# v0_4_5.net
KiCad netlist of a schematic drawn in EAGLE
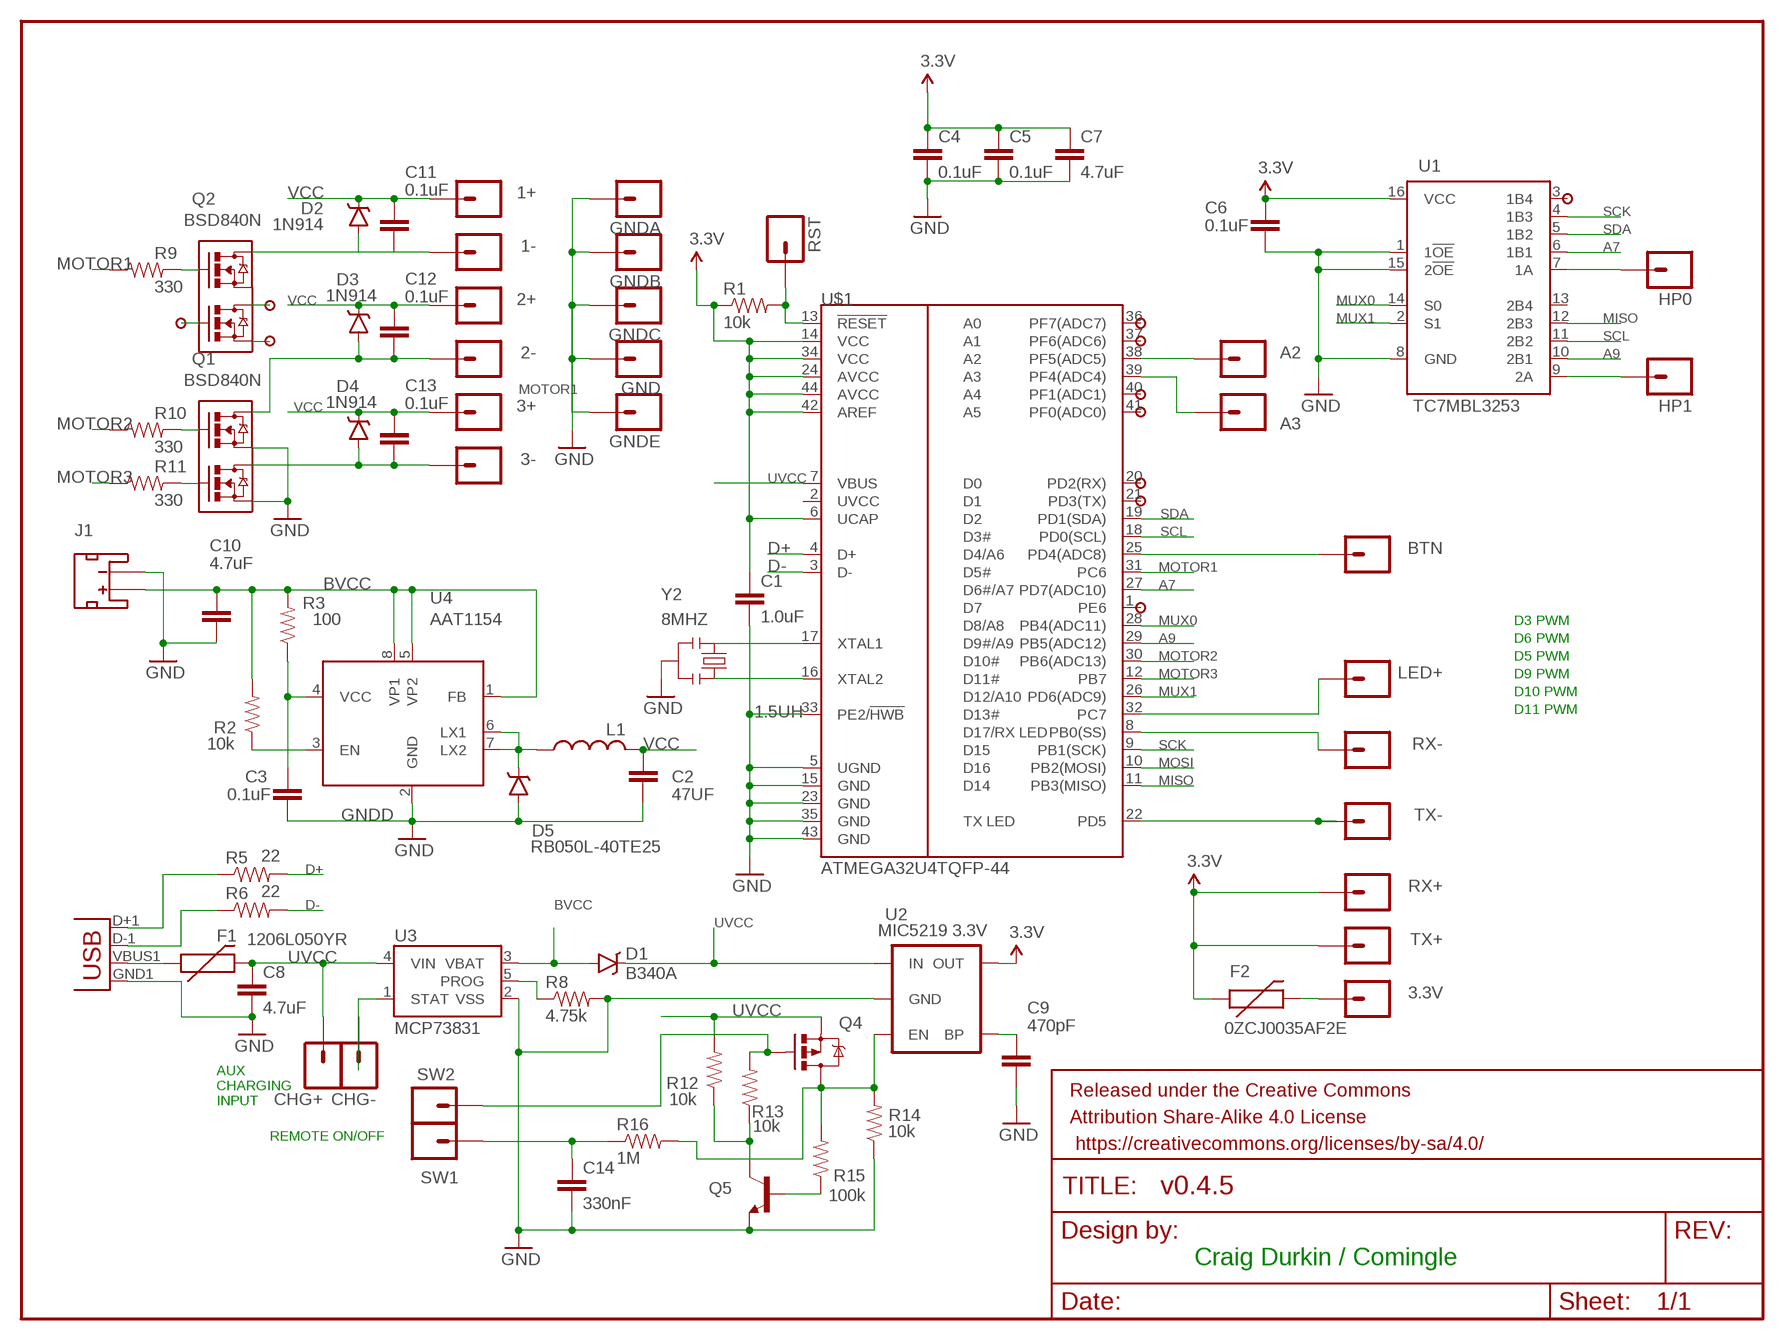
[diagram p0: schematic, sheet 1]

(export (version "E")
  (design (tool "Eeschema 10.0.6"))
  (components
    (comp (ref "1+")
      (value "M01PTH")
      (footprint "eagle-import:1X01")
      (libsource (lib "eagle-import") (part "M01PTH"))
    )
    (comp (ref "1-")
      (value "M01PTH")
      (footprint "eagle-import:1X01")
      (libsource (lib "eagle-import") (part "M01PTH"))
    )
    (comp (ref "2+")
      (value "M01PTH")
      (footprint "eagle-import:1X01")
      (libsource (lib "eagle-import") (part "M01PTH"))
    )
    (comp (ref "2-")
      (value "M01PTH")
      (footprint "eagle-import:1X01")
      (libsource (lib "eagle-import") (part "M01PTH"))
    )
    (comp (ref "3+")
      (value "M01PTH")
      (footprint "eagle-import:1X01")
      (libsource (lib "eagle-import") (part "M01PTH"))
    )
    (comp (ref "3-")
      (value "M01PTH")
      (footprint "eagle-import:1X01")
      (libsource (lib "eagle-import") (part "M01PTH"))
    )
    (comp (ref "3.3V")
      (value "M01PTH")
      (footprint "eagle-import:1X01")
      (libsource (lib "eagle-import") (part "M01PTH"))
    )
    (comp (ref "A2")
      (value "M01PTH")
      (footprint "eagle-import:1X01")
      (libsource (lib "eagle-import") (part "M01PTH"))
    )
    (comp (ref "A3")
      (value "M01PTH")
      (footprint "eagle-import:1X01")
      (libsource (lib "eagle-import") (part "M01PTH"))
    )
    (comp (ref "BTN")
      (value "M01PTH")
      (footprint "eagle-import:1X01")
      (libsource (lib "eagle-import") (part "M01PTH"))
    )
    (comp (ref "C1")
      (value "1.0uF")
      (footprint "eagle-import:0603-CAP")
      (libsource (lib "eagle-import") (part "CAP0603-CAP"))
    )
    (comp (ref "C2")
      (value "47UF")
      (footprint "eagle-import:0805")
      (libsource (lib "eagle-import") (part "v0.4.5_CAP0805"))
    )
    (comp (ref "C3")
      (value "0.1uF")
      (footprint "eagle-import:0603-CAP")
      (libsource (lib "eagle-import") (part "SparkFun-Passives_CAP0603-CAP"))
    )
    (comp (ref "C4")
      (value "0.1uF")
      (footprint "eagle-import:0603-CAP")
      (libsource (lib "eagle-import") (part "SparkFun-Passives_CAP0603-CAP"))
    )
    (comp (ref "C5")
      (value "0.1uF")
      (footprint "eagle-import:0603-CAP")
      (libsource (lib "eagle-import") (part "SparkFun-Passives_CAP0603-CAP"))
    )
    (comp (ref "C6")
      (value "0.1uF")
      (footprint "eagle-import:0603-CAP")
      (libsource (lib "eagle-import") (part "SparkFun-Passives_CAP0603-CAP"))
    )
    (comp (ref "C7")
      (value "4.7uF")
      (footprint "eagle-import:0603-CAP")
      (libsource (lib "eagle-import") (part "SparkFun-Passives_CAP0603-CAP"))
    )
    (comp (ref "C8")
      (value "4.7uF")
      (footprint "eagle-import:1206")
      (libsource (lib "eagle-import") (part "SparkFun-Passives_CAP1206"))
    )
    (comp (ref "C9")
      (value "470pF")
      (footprint "eagle-import:0603-CAP")
      (libsource (lib "eagle-import") (part "CAP0603-CAP"))
    )
    (comp (ref "C10")
      (value "4.7uF")
      (footprint "eagle-import:1206")
      (libsource (lib "eagle-import") (part "SparkFun-Passives_CAP1206"))
    )
    (comp (ref "C11")
      (value "0.1uF")
      (footprint "eagle-import:0603-CAP")
      (libsource (lib "eagle-import") (part "CAP0603-CAP"))
    )
    (comp (ref "C12")
      (value "0.1uF")
      (footprint "eagle-import:0603-CAP")
      (libsource (lib "eagle-import") (part "CAP0603-CAP"))
    )
    (comp (ref "C13")
      (value "0.1uF")
      (footprint "eagle-import:0603-CAP")
      (libsource (lib "eagle-import") (part "CAP0603-CAP"))
    )
    (comp (ref "C14")
      (value "330nF")
      (footprint "eagle-import:0603-CAP")
      (libsource (lib "eagle-import") (part "CAP0603-CAP"))
    )
    (comp (ref "CHG+")
      (value "M01PTH")
      (footprint "eagle-import:1X01")
      (libsource (lib "eagle-import") (part "M01PTH"))
    )
    (comp (ref "CHG-")
      (value "M01PTH")
      (footprint "eagle-import:1X01")
      (libsource (lib "eagle-import") (part "M01PTH"))
    )
    (comp (ref "D1")
      (value "B340A")
      (footprint "eagle-import:SMA-DIODE")
      (libsource (lib "eagle-import") (part "DIODE-SCHOTTKY-B340A"))
    )
    (comp (ref "D2")
      (value "1N914")
      (footprint "eagle-import:SOD-323")
      (libsource (lib "eagle-import") (part "BAT20JFILM"))
    )
    (comp (ref "D3")
      (value "1N914")
      (footprint "eagle-import:SOD-323")
      (libsource (lib "eagle-import") (part "BAT20JFILM"))
    )
    (comp (ref "D4")
      (value "1N914")
      (footprint "eagle-import:SOD-323")
      (libsource (lib "eagle-import") (part "BAT20JFILM"))
    )
    (comp (ref "D5")
      (value "RB050L-40TE25")
      (footprint "eagle-import:SMA-DIODE")
      (libsource (lib "eagle-import") (part "v0.4.5_DIODE-SCHOTTKY-B340A"))
    )
    (comp (ref "F1")
      (value "1206L050YR")
      (footprint "eagle-import:PTC-1206")
      (libsource (lib "eagle-import") (part "PTCSMD"))
    )
    (comp (ref "F2")
      (value "0ZCJ0035AF2E")
      (footprint "eagle-import:PTC-1206")
      (libsource (lib "eagle-import") (part "PTCSMD"))
    )
    (comp (ref "FRAME1")
      (value "FRAME-LETTER")
      (footprint "eagle-import:CREATIVE_COMMONS")
      (libsource (lib "eagle-import") (part "FRAME-LETTER"))
    )
    (comp (ref "GND")
      (value "M01PTH")
      (footprint "eagle-import:1X01")
      (libsource (lib "eagle-import") (part "M01PTH"))
    )
    (comp (ref "GNDA")
      (value "M01PTH")
      (footprint "eagle-import:1X01")
      (libsource (lib "eagle-import") (part "M01PTH"))
    )
    (comp (ref "GNDB")
      (value "M01PTH")
      (footprint "eagle-import:1X01")
      (libsource (lib "eagle-import") (part "M01PTH"))
    )
    (comp (ref "GNDC")
      (value "M01PTH")
      (footprint "eagle-import:1X01")
      (libsource (lib "eagle-import") (part "M01PTH"))
    )
    (comp (ref "GNDE")
      (value "M01PTH")
      (footprint "eagle-import:1X01")
      (libsource (lib "eagle-import") (part "M01PTH"))
    )
    (comp (ref "HP0")
      (value "M01PTH")
      (footprint "eagle-import:1X01")
      (libsource (lib "eagle-import") (part "M01PTH"))
    )
    (comp (ref "HP1")
      (value "M01PTH")
      (footprint "eagle-import:1X01")
      (libsource (lib "eagle-import") (part "M01PTH"))
    )
    (comp (ref "J1")
      (value "JST_2MM_MALE")
      (footprint "eagle-import:JST-2-SMD")
      (libsource (lib "eagle-import") (part "JST_2MM_MALE"))
    )
    (comp (ref "JP4")
      (value "USB")
      (footprint "eagle-import:USB-B-MICRO-SMD_V03")
      (libsource (lib "eagle-import") (part "USB"))
    )
    (comp (ref "L1")
      (value "1.5UH")
      (footprint "eagle-import:CHOKE_5MM")
      (libsource (lib "eagle-import") (part "LQH5BPN1R5NT0L_INDUCTOR"))
    )
    (comp (ref "LED+")
      (value "M01PTH")
      (footprint "eagle-import:1X01")
      (libsource (lib "eagle-import") (part "M01PTH"))
    )
    (comp (ref "PD2")
      (value "040_PAD_030_HOLE")
      (footprint "eagle-import:040_PAD_O30_HOLE")
      (libsource (lib "eagle-import") (part "040_PAD_030_HOLE"))
    )
    (comp (ref "PD3")
      (value "040_PAD_030_HOLE")
      (footprint "eagle-import:040_PAD_O30_HOLE")
      (libsource (lib "eagle-import") (part "040_PAD_030_HOLE"))
    )
    (comp (ref "PD4")
      (value "040_PAD_030_HOLE")
      (footprint "eagle-import:040_PAD_O30_HOLE")
      (libsource (lib "eagle-import") (part "040_PAD_030_HOLE"))
    )
    (comp (ref "PD5")
      (value "040_PAD_030_HOLE")
      (footprint "eagle-import:040_PAD_O30_HOLE")
      (libsource (lib "eagle-import") (part "040_PAD_030_HOLE"))
    )
    (comp (ref "PD6")
      (value "040_PAD_030_HOLE")
      (footprint "eagle-import:040_PAD_O30_HOLE")
      (libsource (lib "eagle-import") (part "040_PAD_030_HOLE"))
    )
    (comp (ref "PD7")
      (value "040_PAD_030_HOLE")
      (footprint "eagle-import:040_PAD_O30_HOLE")
      (libsource (lib "eagle-import") (part "040_PAD_030_HOLE"))
    )
    (comp (ref "PD8")
      (value "040_PAD_030_HOLE")
      (footprint "eagle-import:040_PAD_O30_HOLE")
      (libsource (lib "eagle-import") (part "040_PAD_030_HOLE"))
    )
    (comp (ref "PD9")
      (value "040_PAD_030_HOLE")
      (footprint "eagle-import:040_PAD_O30_HOLE")
      (libsource (lib "eagle-import") (part "040_PAD_030_HOLE"))
    )
    (comp (ref "PD10")
      (value "040_PAD_030_HOLE")
      (footprint "eagle-import:040_PAD_O30_HOLE")
      (libsource (lib "eagle-import") (part "040_PAD_030_HOLE"))
    )
    (comp (ref "PD11")
      (value "040_PAD_030_HOLE")
      (footprint "eagle-import:040_PAD_O30_HOLE")
      (libsource (lib "eagle-import") (part "040_PAD_030_HOLE"))
    )
    (comp (ref "PD12")
      (value "040_PAD_030_HOLE")
      (footprint "eagle-import:040_PAD_O30_HOLE")
      (libsource (lib "eagle-import") (part "040_PAD_030_HOLE"))
    )
    (comp (ref "Q1")
      (value "BSD840N")
      (footprint "eagle-import:PG-SOT-363")
      (libsource (lib "eagle-import") (part "BSD840N"))
    )
    (comp (ref "Q2")
      (value "BSD840N")
      (footprint "eagle-import:PG-SOT-363")
      (libsource (lib "eagle-import") (part "BSD840N"))
    )
    (comp (ref "Q4")
      (value "NTS2101PT1G")
      (footprint "eagle-import:SOT23-3")
      (libsource (lib "eagle-import") (part "MOSFET-PCHANNEL"))
    )
    (comp (ref "Q5")
      (value "MMBT2222A")
      (footprint "eagle-import:SOT23-3")
      (libsource (lib "eagle-import") (part "TRANSISTOR_NPNMMBT2222A"))
    )
    (comp (ref "R1")
      (value "10k")
      (footprint "eagle-import:0603-RES")
      (libsource (lib "eagle-import") (part "RESISTOR0603-RES"))
    )
    (comp (ref "R2")
      (value "10k")
      (footprint "eagle-import:0603-RES")
      (libsource (lib "eagle-import") (part "RESISTOR0603-RES"))
    )
    (comp (ref "R3")
      (value "100")
      (footprint "eagle-import:0603-RES")
      (libsource (lib "eagle-import") (part "RESISTOR0603-RES"))
    )
    (comp (ref "R5")
      (value "22")
      (footprint "eagle-import:0603-RES")
      (libsource (lib "eagle-import") (part "RESISTOR0603-RES"))
    )
    (comp (ref "R6")
      (value "22")
      (footprint "eagle-import:0603-RES")
      (libsource (lib "eagle-import") (part "RESISTOR0603-RES"))
    )
    (comp (ref "R8")
      (value "4.75k")
      (footprint "eagle-import:0603-RES")
      (libsource (lib "eagle-import") (part "RESISTOR0603-RES"))
    )
    (comp (ref "R9")
      (value "330")
      (footprint "eagle-import:0603-RES")
      (libsource (lib "eagle-import") (part "RESISTOR0603-RES"))
    )
    (comp (ref "R10")
      (value "330")
      (footprint "eagle-import:0603-RES")
      (libsource (lib "eagle-import") (part "RESISTOR0603-RES"))
    )
    (comp (ref "R11")
      (value "330")
      (footprint "eagle-import:0603-RES")
      (libsource (lib "eagle-import") (part "RESISTOR0603-RES"))
    )
    (comp (ref "R12")
      (value "10k")
      (footprint "eagle-import:0603-RES")
      (libsource (lib "eagle-import") (part "RESISTOR0603-RES"))
    )
    (comp (ref "R13")
      (value "10k")
      (footprint "eagle-import:0603-RES")
      (libsource (lib "eagle-import") (part "RESISTOR0603-RES"))
    )
    (comp (ref "R14")
      (value "10k")
      (footprint "eagle-import:0603-RES")
      (libsource (lib "eagle-import") (part "RESISTOR0603-RES"))
    )
    (comp (ref "R15")
      (value "100k")
      (footprint "eagle-import:0603-RES")
      (libsource (lib "eagle-import") (part "RESISTOR0603-RES"))
    )
    (comp (ref "R16")
      (value "1M")
      (footprint "eagle-import:0603-RES")
      (libsource (lib "eagle-import") (part "RESISTOR0603-RES"))
    )
    (comp (ref "RST")
      (value "M01PTH")
      (footprint "eagle-import:1X01")
      (libsource (lib "eagle-import") (part "M01PTH"))
    )
    (comp (ref "RX+")
      (value "M01PTH")
      (footprint "eagle-import:1X01")
      (libsource (lib "eagle-import") (part "M01PTH"))
    )
    (comp (ref "RX-")
      (value "M01PTH")
      (footprint "eagle-import:1X01")
      (libsource (lib "eagle-import") (part "M01PTH"))
    )
    (comp (ref "SW1")
      (value "M01PTH")
      (footprint "eagle-import:1X01")
      (libsource (lib "eagle-import") (part "M01PTH"))
    )
    (comp (ref "SW2")
      (value "M01PTH")
      (footprint "eagle-import:1X01")
      (libsource (lib "eagle-import") (part "M01PTH"))
    )
    (comp (ref "TX+")
      (value "M01PTH")
      (footprint "eagle-import:1X01")
      (libsource (lib "eagle-import") (part "M01PTH"))
    )
    (comp (ref "TX-")
      (value "M01PTH")
      (footprint "eagle-import:1X01")
      (libsource (lib "eagle-import") (part "M01PTH"))
    )
    (comp (ref "U$1")
      (value "ATMEGA32U4TQFP-44")
      (footprint "eagle-import:TQFP44")
      (libsource (lib "eagle-import") (part "ATMEGA32U4TQFP-44"))
    )
    (comp (ref "U1")
      (value "TC7MBL3253")
      (footprint "eagle-import:SSOP16-PRACTICE")
      (libsource (lib "eagle-import") (part "TC7MBL3253"))
    )
    (comp (ref "U2")
      (value "MIC5219 3.3V")
      (footprint "eagle-import:SOT23-5")
      (libsource (lib "eagle-import") (part "V_REG_MIC52193.3V"))
    )
    (comp (ref "U3")
      (value "MCP73831")
      (footprint "eagle-import:SOT23-5")
      (libsource (lib "eagle-import") (part "MCP73831"))
    )
    (comp (ref "U4")
      (value "AAT1154")
      (footprint "eagle-import:SOP-8")
      (libsource (lib "eagle-import") (part "AAT1154"))
    )
    (comp (ref "Y2")
      (value "8MHZ")
      (footprint "eagle-import:RESONATOR-SMD")
      (libsource (lib "eagle-import") (part "RESONATOR8MHZ"))
    )
  )
  (nets
    (net (code "1") (name "/A7") (class "Default")
      (node (ref "U$1") (pin "27") (pinfunction "PD7(ADC10)_27") (pintype "bidirectional"))
      (node (ref "U1") (pin "6") (pinfunction "1B1_6") (pintype "bidirectional"))
    )
    (net (code "2") (name "/A9") (class "Default")
      (node (ref "U$1") (pin "29") (pinfunction "PB5(ADC12)_29") (pintype "bidirectional"))
      (node (ref "U1") (pin "10") (pinfunction "2B1_10") (pintype "bidirectional"))
    )
    (net (code "3") (name "/BVCC") (class "Default")
      (node (ref "C10") (pin "1") (pinfunction "1_1") (pintype "passive"))
      (node (ref "D1") (pin "A") (pinfunction "A_A") (pintype "passive"))
      (node (ref "J1") (pin "2") (pinfunction "+_2") (pintype "bidirectional"))
      (node (ref "R2") (pin "2") (pinfunction "2_2") (pintype "passive"))
      (node (ref "R3") (pin "2") (pinfunction "2_2") (pintype "passive"))
      (node (ref "U3") (pin "3") (pinfunction "VBAT_3") (pintype "power_in"))
      (node (ref "U4") (pin "1") (pinfunction "FB_1") (pintype "input"))
      (node (ref "U4") (pin "5") (pinfunction "VP2_5") (pintype "power_in"))
      (node (ref "U4") (pin "8") (pinfunction "VP1_8") (pintype "power_in"))
    )
    (net (code "4") (name "/D+") (class "Default")
      (node (ref "R5") (pin "2") (pinfunction "2_2") (pintype "passive"))
      (node (ref "U$1") (pin "4") (pinfunction "D+_4") (pintype "bidirectional"))
    )
    (net (code "5") (name "/D-") (class "Default")
      (node (ref "R6") (pin "2") (pinfunction "2_2") (pintype "passive"))
      (node (ref "U$1") (pin "3") (pinfunction "D-_3") (pintype "bidirectional"))
    )
    (net (code "6") (name "/MISO") (class "Default")
      (node (ref "U$1") (pin "11") (pinfunction "PB3(MISO)_11") (pintype "bidirectional"))
      (node (ref "U1") (pin "12") (pinfunction "2B3_12") (pintype "bidirectional"))
    )
    (net (code "7") (name "/MOSI") (class "Default")
      (node (ref "U$1") (pin "10") (pinfunction "PB2(MOSI)_10") (pintype "bidirectional"))
    )
    (net (code "8") (name "/MOTOR1") (class "Default")
      (node (ref "R9") (pin "1") (pinfunction "1_1") (pintype "passive"))
      (node (ref "U$1") (pin "31") (pinfunction "PC6_31") (pintype "bidirectional"))
    )
    (net (code "9") (name "/MOTOR2") (class "Default")
      (node (ref "R10") (pin "1") (pinfunction "1_1") (pintype "passive"))
      (node (ref "U$1") (pin "30") (pinfunction "PB6(ADC13)_30") (pintype "bidirectional"))
    )
    (net (code "10") (name "/MOTOR3") (class "Default")
      (node (ref "R11") (pin "1") (pinfunction "1_1") (pintype "passive"))
      (node (ref "U$1") (pin "12") (pinfunction "PB7_12") (pintype "bidirectional"))
    )
    (net (code "11") (name "/MUX0") (class "Default")
      (node (ref "U$1") (pin "28") (pinfunction "PB4(ADC11)_28") (pintype "bidirectional"))
      (node (ref "U1") (pin "14") (pinfunction "S0_14") (pintype "bidirectional"))
    )
    (net (code "12") (name "/MUX1") (class "Default")
      (node (ref "U$1") (pin "26") (pinfunction "PD6(ADC9)_26") (pintype "bidirectional"))
      (node (ref "U1") (pin "2") (pinfunction "S1_2") (pintype "bidirectional"))
    )
    (net (code "13") (name "/SCK") (class "Default")
      (node (ref "U$1") (pin "9") (pinfunction "PB1(SCK)_9") (pintype "bidirectional"))
      (node (ref "U1") (pin "4") (pinfunction "1B3_4") (pintype "bidirectional"))
    )
    (net (code "14") (name "/SCL") (class "Default")
      (node (ref "U$1") (pin "18") (pinfunction "PD0(SCL)_18") (pintype "bidirectional"))
      (node (ref "U1") (pin "11") (pinfunction "2B2_11") (pintype "bidirectional"))
    )
    (net (code "15") (name "/SDA") (class "Default")
      (node (ref "U$1") (pin "19") (pinfunction "PD1(SDA)_19") (pintype "bidirectional"))
      (node (ref "U1") (pin "5") (pinfunction "1B2_5") (pintype "bidirectional"))
    )
    (net (code "16") (name "/UVCC") (class "Default")
      (node (ref "C8") (pin "1") (pinfunction "1_1") (pintype "passive"))
      (node (ref "CHG+") (pin "1") (pinfunction "1_1") (pintype "passive"))
      (node (ref "D1") (pin "C") (pinfunction "C_C") (pintype "passive"))
      (node (ref "F1") (pin "2") (pinfunction "2_2") (pintype "bidirectional"))
      (node (ref "Q4") (pin "2") (pinfunction "S_2") (pintype "passive"))
      (node (ref "R12") (pin "2") (pinfunction "2_2") (pintype "passive"))
      (node (ref "U$1") (pin "7") (pinfunction "VBUS_7") (pintype "bidirectional"))
      (node (ref "U2") (pin "1") (pinfunction "IN_1") (pintype "input"))
      (node (ref "U3") (pin "4") (pinfunction "VIN_4") (pintype "power_in"))
    )
    (net (code "17") (name "3.3V") (class "Default")
      (node (ref "1+") (pin "1") (pinfunction "1_1") (pintype "passive"))
      (node (ref "2+") (pin "1") (pinfunction "1_1") (pintype "passive"))
      (node (ref "3+") (pin "1") (pinfunction "1_1") (pintype "passive"))
      (node (ref "C1") (pin "1") (pinfunction "1_1") (pintype "passive"))
      (node (ref "C11") (pin "1") (pinfunction "1_1") (pintype "passive"))
      (node (ref "C12") (pin "1") (pinfunction "1_1") (pintype "passive"))
      (node (ref "C13") (pin "1") (pinfunction "1_1") (pintype "passive"))
      (node (ref "C2") (pin "1") (pinfunction "1_1") (pintype "passive"))
      (node (ref "C4") (pin "1") (pinfunction "1_1") (pintype "passive"))
      (node (ref "C5") (pin "1") (pinfunction "1_1") (pintype "passive"))
      (node (ref "C6") (pin "1") (pinfunction "1_1") (pintype "passive"))
      (node (ref "C7") (pin "1") (pinfunction "1_1") (pintype "passive"))
      (node (ref "D2") (pin "C") (pinfunction "C_C") (pintype "passive"))
      (node (ref "D3") (pin "C") (pinfunction "C_C") (pintype "passive"))
      (node (ref "D4") (pin "C") (pinfunction "C_C") (pintype "passive"))
      (node (ref "F2") (pin "1") (pinfunction "1_1") (pintype "bidirectional"))
      (node (ref "L1") (pin "2") (pinfunction "2_2") (pintype "passive"))
      (node (ref "R1") (pin "1") (pinfunction "1_1") (pintype "passive"))
      (node (ref "RX+") (pin "1") (pinfunction "1_1") (pintype "passive"))
      (node (ref "TX+") (pin "1") (pinfunction "1_1") (pintype "passive"))
      (node (ref "U$1") (pin "14") (pinfunction "VCC_14") (pintype "bidirectional"))
      (node (ref "U$1") (pin "24") (pinfunction "AVCC_24") (pintype "bidirectional"))
      (node (ref "U$1") (pin "34") (pinfunction "VCC_34") (pintype "bidirectional"))
      (node (ref "U$1") (pin "42") (pinfunction "AREF_42") (pintype "bidirectional"))
      (node (ref "U$1") (pin "44") (pinfunction "AVCC_44") (pintype "bidirectional"))
      (node (ref "U$1") (pin "6") (pinfunction "UCAP_6") (pintype "bidirectional"))
      (node (ref "U1") (pin "16") (pinfunction "VCC_16") (pintype "power_in"))
      (node (ref "U2") (pin "5") (pinfunction "OUT_5") (pintype "passive"))
    )
    (net (code "18") (name "GND") (class "Default")
      (node (ref "C1") (pin "2") (pinfunction "2_2") (pintype "passive"))
      (node (ref "C10") (pin "2") (pinfunction "2_2") (pintype "passive"))
      (node (ref "C14") (pin "2") (pinfunction "2_2") (pintype "passive"))
      (node (ref "C2") (pin "2") (pinfunction "2_2") (pintype "passive"))
      (node (ref "C3") (pin "2") (pinfunction "2_2") (pintype "passive"))
      (node (ref "C4") (pin "2") (pinfunction "2_2") (pintype "passive"))
      (node (ref "C5") (pin "2") (pinfunction "2_2") (pintype "passive"))
      (node (ref "C6") (pin "2") (pinfunction "2_2") (pintype "passive"))
      (node (ref "C7") (pin "2") (pinfunction "2_2") (pintype "passive"))
      (node (ref "C8") (pin "2") (pinfunction "2_2") (pintype "passive"))
      (node (ref "C9") (pin "2") (pinfunction "2_2") (pintype "passive"))
      (node (ref "D5") (pin "A") (pinfunction "A_A") (pintype "passive"))
      (node (ref "GND") (pin "1") (pinfunction "1_1") (pintype "passive"))
      (node (ref "GNDA") (pin "1") (pinfunction "1_1") (pintype "passive"))
      (node (ref "GNDB") (pin "1") (pinfunction "1_1") (pintype "passive"))
      (node (ref "GNDC") (pin "1") (pinfunction "1_1") (pintype "passive"))
      (node (ref "GNDE") (pin "1") (pinfunction "1_1") (pintype "passive"))
      (node (ref "J1") (pin "1") (pinfunction "-_1") (pintype "bidirectional"))
      (node (ref "JP4") (pin "GND1") (pinfunction "GND_GND1") (pintype "bidirectional"))
      (node (ref "Q1") (pin "1") (pinfunction "S_1") (pintype "passive"))
      (node (ref "Q1") (pin "4") (pinfunction "S1_4") (pintype "passive"))
      (node (ref "Q5") (pin "2") (pinfunction "E_2") (pintype "passive"))
      (node (ref "R14") (pin "1") (pinfunction "1_1") (pintype "passive"))
      (node (ref "R8") (pin "2") (pinfunction "2_2") (pintype "passive"))
      (node (ref "U$1") (pin "15") (pinfunction "GND_15") (pintype "bidirectional"))
      (node (ref "U$1") (pin "23") (pinfunction "GND_23") (pintype "bidirectional"))
      (node (ref "U$1") (pin "33") (pinfunction "PE2/~{HWB}_33") (pintype "bidirectional"))
      (node (ref "U$1") (pin "35") (pinfunction "GND_35") (pintype "bidirectional"))
      (node (ref "U$1") (pin "43") (pinfunction "GND_43") (pintype "bidirectional"))
      (node (ref "U$1") (pin "5") (pinfunction "UGND_5") (pintype "bidirectional"))
      (node (ref "U1") (pin "1") (pinfunction "1~{OE}_1") (pintype "input"))
      (node (ref "U1") (pin "15") (pinfunction "2~{OE}_15") (pintype "input"))
      (node (ref "U1") (pin "8") (pinfunction "GND_8") (pintype "power_in"))
      (node (ref "U2") (pin "2") (pinfunction "GND_2") (pintype "input"))
      (node (ref "U3") (pin "2") (pinfunction "VSS_2") (pintype "power_in"))
      (node (ref "U4") (pin "2") (pinfunction "GND_2") (pintype "power_in"))
      (node (ref "Y2") (pin "2") (pinfunction "2_2") (pintype "passive"))
    )
    (net (code "19") (name "Net-(3.3V-Pad1)") (class "Default")
      (node (ref "3.3V") (pin "1") (pinfunction "1_1") (pintype "passive"))
      (node (ref "F2") (pin "2") (pinfunction "2_2") (pintype "bidirectional"))
    )
    (net (code "20") (name "Net-(C14-Pad1)") (class "Default")
      (node (ref "C14") (pin "1") (pinfunction "1_1") (pintype "passive"))
      (node (ref "R16") (pin "1") (pinfunction "1_1") (pintype "passive"))
      (node (ref "SW1") (pin "1") (pinfunction "1_1") (pintype "passive"))
    )
    (net (code "21") (name "Net-(JP4-D+)") (class "Default")
      (node (ref "JP4") (pin "D+1") (pinfunction "D+_D+1") (pintype "bidirectional"))
      (node (ref "R5") (pin "1") (pinfunction "1_1") (pintype "passive"))
    )
    (net (code "22") (name "Net-(JP4-D-)") (class "Default")
      (node (ref "JP4") (pin "D-1") (pinfunction "D-_D-1") (pintype "bidirectional"))
      (node (ref "R6") (pin "1") (pinfunction "1_1") (pintype "passive"))
    )
    (net (code "23") (name "Net-(JP4-VBUS)") (class "Default")
      (node (ref "F1") (pin "1") (pinfunction "1_1") (pintype "bidirectional"))
      (node (ref "JP4") (pin "VBUS1") (pinfunction "VBUS_VBUS1") (pintype "bidirectional"))
    )
    (net (code "24") (name "Net-(Q1-D)") (class "Default")
      (node (ref "2-") (pin "1") (pinfunction "1_1") (pintype "passive"))
      (node (ref "C12") (pin "2") (pinfunction "2_2") (pintype "passive"))
      (node (ref "D3") (pin "A") (pinfunction "A_A") (pintype "passive"))
      (node (ref "Q1") (pin "6") (pinfunction "D_6") (pintype "passive"))
    )
    (net (code "25") (name "Net-(Q1-D1)") (class "Default")
      (node (ref "3-") (pin "1") (pinfunction "1_1") (pintype "passive"))
      (node (ref "C13") (pin "2") (pinfunction "2_2") (pintype "passive"))
      (node (ref "D4") (pin "A") (pinfunction "A_A") (pintype "passive"))
      (node (ref "Q1") (pin "3") (pinfunction "D1_3") (pintype "passive"))
    )
    (net (code "26") (name "Net-(Q1-G)") (class "Default")
      (node (ref "Q1") (pin "2") (pinfunction "G_2") (pintype "passive"))
      (node (ref "R10") (pin "2") (pinfunction "2_2") (pintype "passive"))
    )
    (net (code "27") (name "Net-(Q1-G1)") (class "Default")
      (node (ref "Q1") (pin "5") (pinfunction "G1_5") (pintype "passive"))
      (node (ref "R11") (pin "2") (pinfunction "2_2") (pintype "passive"))
    )
    (net (code "28") (name "Net-(Q2-D)") (class "Default")
      (node (ref "1-") (pin "1") (pinfunction "1_1") (pintype "passive"))
      (node (ref "C11") (pin "2") (pinfunction "2_2") (pintype "passive"))
      (node (ref "D2") (pin "A") (pinfunction "A_A") (pintype "passive"))
      (node (ref "Q2") (pin "6") (pinfunction "D_6") (pintype "passive"))
    )
    (net (code "29") (name "Net-(Q2-D1)") (class "Default")
      (node (ref "PD12") (pin "1") (pinfunction "1_1") (pintype "passive"))
      (node (ref "Q2") (pin "3") (pinfunction "D1_3") (pintype "passive"))
    )
    (net (code "30") (name "Net-(Q2-G)") (class "Default")
      (node (ref "Q2") (pin "2") (pinfunction "G_2") (pintype "passive"))
      (node (ref "R9") (pin "2") (pinfunction "2_2") (pintype "passive"))
    )
    (net (code "31") (name "Net-(Q2-G1)") (class "Default")
      (node (ref "PD10") (pin "1") (pinfunction "1_1") (pintype "passive"))
      (node (ref "Q2") (pin "5") (pinfunction "G1_5") (pintype "passive"))
    )
    (net (code "32") (name "Net-(Q2-S1)") (class "Default")
      (node (ref "PD11") (pin "1") (pinfunction "1_1") (pintype "passive"))
      (node (ref "Q2") (pin "4") (pinfunction "S1_4") (pintype "passive"))
    )
    (net (code "33") (name "Net-(Q4-D)") (class "Default")
      (node (ref "Q4") (pin "3") (pinfunction "D_3") (pintype "passive"))
      (node (ref "R14") (pin "2") (pinfunction "2_2") (pintype "passive"))
      (node (ref "R15") (pin "2") (pinfunction "2_2") (pintype "passive"))
      (node (ref "R16") (pin "2") (pinfunction "2_2") (pintype "passive"))
      (node (ref "U2") (pin "3") (pinfunction "EN_3") (pintype "input"))
    )
    (net (code "34") (name "Net-(Q4-G)") (class "Default")
      (node (ref "Q4") (pin "1") (pinfunction "G_1") (pintype "passive"))
      (node (ref "R13") (pin "2") (pinfunction "2_2") (pintype "passive"))
      (node (ref "SW2") (pin "1") (pinfunction "1_1") (pintype "passive"))
    )
    (net (code "35") (name "Net-(Q5-B)") (class "Default")
      (node (ref "Q5") (pin "1") (pinfunction "B_1") (pintype "passive"))
      (node (ref "R15") (pin "1") (pinfunction "1_1") (pintype "passive"))
    )
    (net (code "36") (name "Net-(Q5-C)") (class "Default")
      (node (ref "Q5") (pin "3") (pinfunction "C_3") (pintype "passive"))
      (node (ref "R12") (pin "1") (pinfunction "1_1") (pintype "passive"))
      (node (ref "R13") (pin "1") (pinfunction "1_1") (pintype "passive"))
    )
    (net (code "37") (name "Net-(U$1-PB0(SS))") (class "Default")
      (node (ref "RX-") (pin "1") (pinfunction "1_1") (pintype "passive"))
      (node (ref "U$1") (pin "8") (pinfunction "PB0(SS)_8") (pintype "bidirectional"))
    )
    (net (code "38") (name "Net-(U$1-PC7)") (class "Default")
      (node (ref "LED+") (pin "1") (pinfunction "1_1") (pintype "passive"))
      (node (ref "U$1") (pin "32") (pinfunction "PC7_32") (pintype "bidirectional"))
    )
    (net (code "39") (name "Net-(U$1-PD2(RX))") (class "Default")
      (node (ref "PD4") (pin "1") (pinfunction "1_1") (pintype "passive"))
      (node (ref "U$1") (pin "20") (pinfunction "PD2(RX)_20") (pintype "bidirectional"))
    )
    (net (code "40") (name "Net-(U$1-PD3(TX))") (class "Default")
      (node (ref "PD3") (pin "1") (pinfunction "1_1") (pintype "passive"))
      (node (ref "U$1") (pin "21") (pinfunction "PD3(TX)_21") (pintype "bidirectional"))
    )
    (net (code "41") (name "Net-(U$1-PD4(ADC8))") (class "Default")
      (node (ref "BTN") (pin "1") (pinfunction "1_1") (pintype "passive"))
      (node (ref "U$1") (pin "25") (pinfunction "PD4(ADC8)_25") (pintype "bidirectional"))
    )
    (net (code "42") (name "Net-(U$1-PD5)") (class "Default")
      (node (ref "TX-") (pin "1") (pinfunction "1_1") (pintype "passive"))
      (node (ref "U$1") (pin "22") (pinfunction "PD5_22") (pintype "bidirectional"))
    )
    (net (code "43") (name "Net-(U$1-PE6)") (class "Default")
      (node (ref "PD9") (pin "1") (pinfunction "1_1") (pintype "passive"))
      (node (ref "U$1") (pin "1") (pinfunction "PE6_1") (pintype "bidirectional"))
    )
    (net (code "44") (name "Net-(U$1-PF0(ADC0))") (class "Default")
      (node (ref "PD5") (pin "1") (pinfunction "1_1") (pintype "passive"))
      (node (ref "U$1") (pin "41") (pinfunction "PF0(ADC0)_41") (pintype "bidirectional"))
    )
    (net (code "45") (name "Net-(U$1-PF1(ADC1))") (class "Default")
      (node (ref "PD6") (pin "1") (pinfunction "1_1") (pintype "passive"))
      (node (ref "U$1") (pin "40") (pinfunction "PF1(ADC1)_40") (pintype "bidirectional"))
    )
    (net (code "46") (name "Net-(U$1-PF4(ADC4))") (class "Default")
      (node (ref "A3") (pin "1") (pinfunction "1_1") (pintype "passive"))
      (node (ref "U$1") (pin "39") (pinfunction "PF4(ADC4)_39") (pintype "bidirectional"))
    )
    (net (code "47") (name "Net-(U$1-PF5(ADC5))") (class "Default")
      (node (ref "A2") (pin "1") (pinfunction "1_1") (pintype "passive"))
      (node (ref "U$1") (pin "38") (pinfunction "PF5(ADC5)_38") (pintype "bidirectional"))
    )
    (net (code "48") (name "Net-(U$1-PF6(ADC6))") (class "Default")
      (node (ref "PD7") (pin "1") (pinfunction "1_1") (pintype "passive"))
      (node (ref "U$1") (pin "37") (pinfunction "PF6(ADC6)_37") (pintype "bidirectional"))
    )
    (net (code "49") (name "Net-(U$1-PF7(ADC7))") (class "Default")
      (node (ref "PD8") (pin "1") (pinfunction "1_1") (pintype "passive"))
      (node (ref "U$1") (pin "36") (pinfunction "PF7(ADC7)_36") (pintype "bidirectional"))
    )
    (net (code "50") (name "Net-(U$1-XTAL1)") (class "Default")
      (node (ref "U$1") (pin "17") (pinfunction "XTAL1_17") (pintype "bidirectional"))
      (node (ref "Y2") (pin "1") (pinfunction "1_1") (pintype "passive"))
    )
    (net (code "51") (name "Net-(U$1-XTAL2)") (class "Default")
      (node (ref "U$1") (pin "16") (pinfunction "XTAL2_16") (pintype "bidirectional"))
      (node (ref "Y2") (pin "3") (pinfunction "3_3") (pintype "passive"))
    )
    (net (code "52") (name "Net-(U$1-~{RESET})") (class "Default")
      (node (ref "R1") (pin "2") (pinfunction "2_2") (pintype "passive"))
      (node (ref "RST") (pin "1") (pinfunction "1_1") (pintype "passive"))
      (node (ref "U$1") (pin "13") (pinfunction "~{RESET}_13") (pintype "bidirectional"))
    )
    (net (code "53") (name "Net-(U1-1A)") (class "Default")
      (node (ref "HP0") (pin "1") (pinfunction "1_1") (pintype "passive"))
      (node (ref "U1") (pin "7") (pinfunction "1A_7") (pintype "bidirectional"))
    )
    (net (code "54") (name "Net-(U1-1B4)") (class "Default")
      (node (ref "PD2") (pin "1") (pinfunction "1_1") (pintype "passive"))
      (node (ref "U1") (pin "3") (pinfunction "1B4_3") (pintype "bidirectional"))
    )
    (net (code "55") (name "Net-(U1-2A)") (class "Default")
      (node (ref "HP1") (pin "1") (pinfunction "1_1") (pintype "passive"))
      (node (ref "U1") (pin "9") (pinfunction "2A_9") (pintype "bidirectional"))
    )
    (net (code "56") (name "Net-(U2-BP)") (class "Default")
      (node (ref "C9") (pin "1") (pinfunction "1_1") (pintype "passive"))
      (node (ref "U2") (pin "4") (pinfunction "BP_4") (pintype "input"))
    )
    (net (code "57") (name "Net-(U3-PROG)") (class "Default")
      (node (ref "R8") (pin "1") (pinfunction "1_1") (pintype "passive"))
      (node (ref "U3") (pin "5") (pinfunction "PROG_5") (pintype "bidirectional"))
    )
    (net (code "58") (name "Net-(U3-STAT)") (class "Default")
      (node (ref "CHG-") (pin "1") (pinfunction "1_1") (pintype "passive"))
      (node (ref "U3") (pin "1") (pinfunction "STAT_1") (pintype "output"))
    )
    (net (code "59") (name "Net-(U4-EN)") (class "Default")
      (node (ref "R2") (pin "1") (pinfunction "1_1") (pintype "passive"))
      (node (ref "U4") (pin "3") (pinfunction "EN_3") (pintype "input"))
    )
    (net (code "60") (name "Net-(U4-LX1)") (class "Default")
      (node (ref "D5") (pin "C") (pinfunction "C_C") (pintype "passive"))
      (node (ref "L1") (pin "1") (pinfunction "1_1") (pintype "passive"))
      (node (ref "U4") (pin "6") (pinfunction "LX1_6") (pintype "output"))
      (node (ref "U4") (pin "7") (pinfunction "LX2_7") (pintype "output"))
    )
    (net (code "61") (name "Net-(U4-VCC)") (class "Default")
      (node (ref "C3") (pin "1") (pinfunction "1_1") (pintype "passive"))
      (node (ref "R3") (pin "1") (pinfunction "1_1") (pintype "passive"))
      (node (ref "U4") (pin "4") (pinfunction "VCC_4") (pintype "input"))
    )
    (net (code "62") (name "unconnected-(J1-PAD1-PadNC1)") (class "Default")
      (node (ref "J1") (pin "NC1") (pinfunction "PAD1_NC1") (pintype "bidirectional"))
    )
    (net (code "63") (name "unconnected-(J1-PAD2-PadNC2)") (class "Default")
      (node (ref "J1") (pin "NC2") (pinfunction "PAD2_NC2") (pintype "bidirectional"))
    )
    (net (code "64") (name "unconnected-(Q2-S-Pad1)") (class "Default")
      (node (ref "Q2") (pin "1") (pinfunction "S_1") (pintype "passive"))
    )
    (net (code "65") (name "unconnected-(U$1-UVCC-Pad2)") (class "Default")
      (node (ref "U$1") (pin "2") (pinfunction "UVCC_2") (pintype "bidirectional"))
    )
    (net (code "66") (name "unconnected-(U1-2B4-Pad13)") (class "Default")
      (node (ref "U1") (pin "13") (pinfunction "2B4_13") (pintype "bidirectional"))
    )
  )
)
